# Stepper_control.net
KiCad netlist of a schematic drawn in Altium Designer
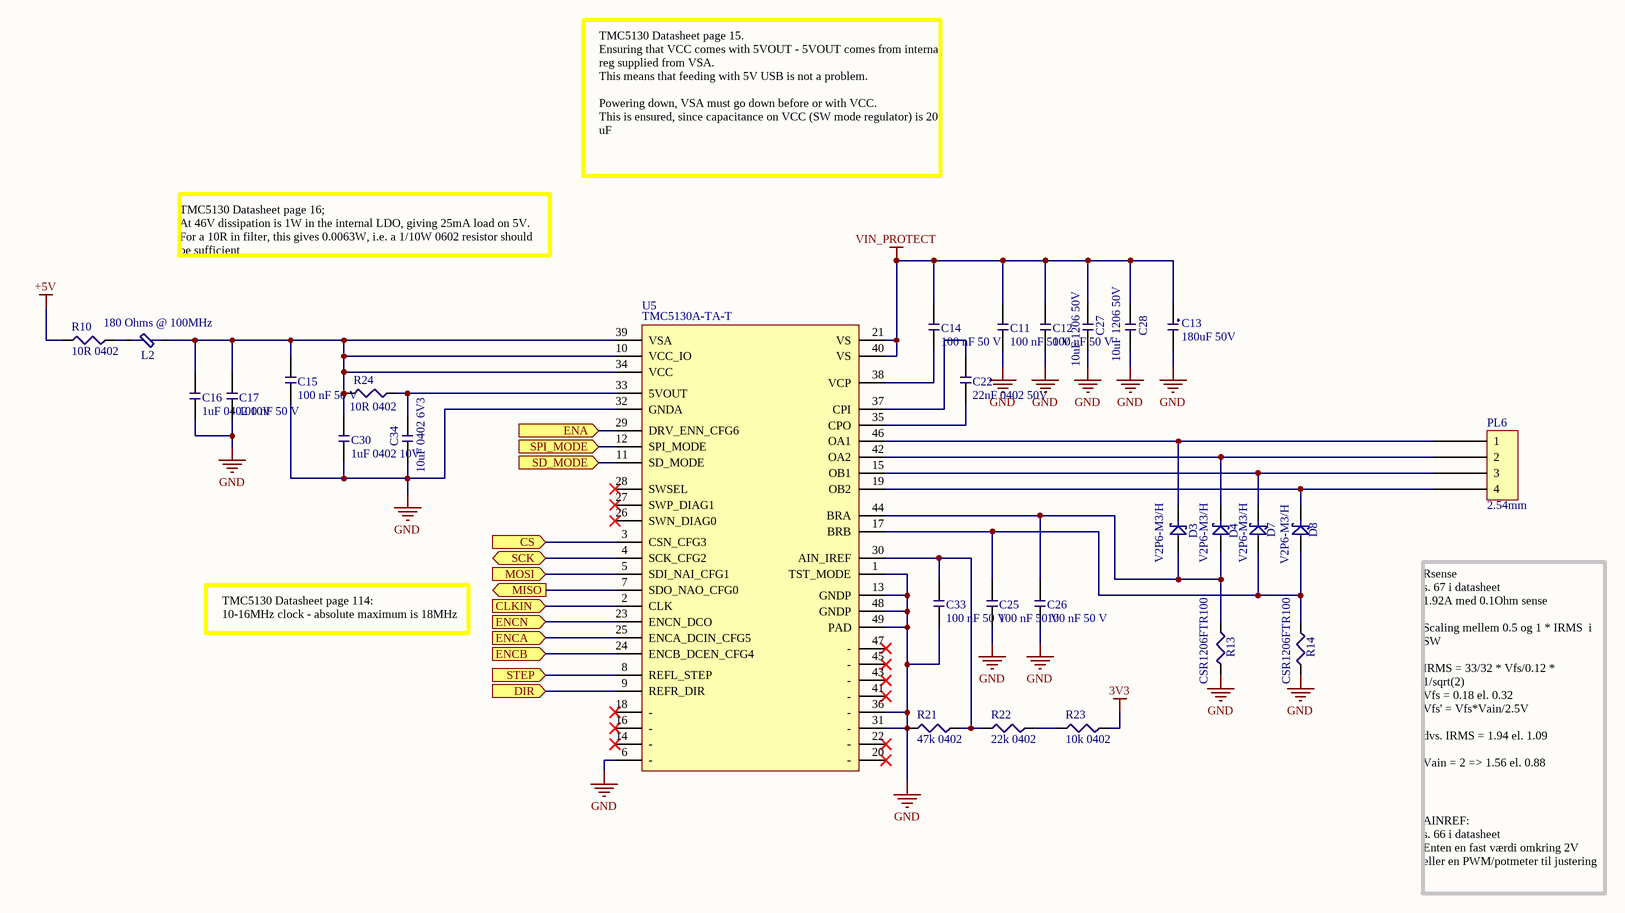
[diagram p0: Stepper_control.SchDoc]

(export (version "E")
  (design (tool "Eeschema 10.0.6"))
  (components
    (comp (ref "C11")
      (value "100 nF 50 V")
      (footprint "CAP_0402")
      (description "Multilayer Ceramic Capacitors MLCC - SMD/SMT .1uF 50Volts X7R +/-10% 0402 STD")
      (fields (field (name "TOLERANCE") "10%") (field (name "VOLTAGE") "50 V"))
      (libsource (lib "ON Development Vault") (part "Capacitor"))
    )
    (comp (ref "C12")
      (value "100 nF 50 V")
      (footprint "CAP_0402")
      (description "Multilayer Ceramic Capacitors MLCC - SMD/SMT .1uF 50Volts X7R +/-10% 0402 STD")
      (fields (field (name "TOLERANCE") "10%") (field (name "VOLTAGE") "50 V"))
      (libsource (lib "ON Development Vault") (part "Capacitor"))
    )
    (comp (ref "C13")
      (value "180uF 50V")
      (footprint "Capacitor 8x22")
      (description "180UF 20% 50V 105DEG RADIAL")
      (fields (field (name "TOLERANCE") "20%"))
      (libsource (lib "ON Development Vault") (part "Polar capacitor"))
    )
    (comp (ref "C14")
      (value "100 nF 50 V")
      (footprint "CAP_0402")
      (description "Multilayer Ceramic Capacitors MLCC - SMD/SMT .1uF 50Volts X7R +/-10% 0402 STD")
      (fields (field (name "TOLERANCE") "10%") (field (name "VOLTAGE") "50 V"))
      (libsource (lib "ON Development Vault") (part "Capacitor"))
    )
    (comp (ref "C15")
      (value "100 nF 50 V")
      (footprint "CAP_0402")
      (description "Multilayer Ceramic Capacitors MLCC - SMD/SMT .1uF 50Volts X7R +/-10% 0402 STD")
      (fields (field (name "TOLERANCE") "10%") (field (name "VOLTAGE") "50 V"))
      (libsource (lib "ON Development Vault") (part "Capacitor"))
    )
    (comp (ref "C16")
      (value "1uF 0402 10V")
      (footprint "CAP_0402")
      (description "1uF 0402 10V 10% X5R")
      (fields (field (name "TOLERANCE") "10%") (field (name "VOLTAGE") "10 V"))
      (libsource (lib "ON Development Vault") (part "Capacitor"))
    )
    (comp (ref "C17")
      (value "100 nF 50 V")
      (footprint "CAP_0402")
      (description "Multilayer Ceramic Capacitors MLCC - SMD/SMT .1uF 50Volts X7R +/-10% 0402 STD")
      (fields (field (name "TOLERANCE") "10%") (field (name "VOLTAGE") "50 V"))
      (libsource (lib "ON Development Vault") (part "Capacitor"))
    )
    (comp (ref "C22")
      (value "22nF 0402 50V")
      (footprint "CAP_0402")
      (description "22nF 0402 50V X7R 10%")
      (fields (field (name "TOLERANCE") "10%") (field (name "VOLTAGE") "50V"))
      (libsource (lib "ON Development Vault") (part "Capacitor"))
    )
    (comp (ref "C25")
      (value "100 nF 50 V")
      (footprint "CAP_0402")
      (description "Multilayer Ceramic Capacitors MLCC - SMD/SMT .1uF 50Volts X7R +/-10% 0402 STD")
      (fields (field (name "TOLERANCE") "10%") (field (name "VOLTAGE") "50 V"))
      (libsource (lib "ON Development Vault") (part "Capacitor"))
    )
    (comp (ref "C26")
      (value "100 nF 50 V")
      (footprint "CAP_0402")
      (description "Multilayer Ceramic Capacitors MLCC - SMD/SMT .1uF 50Volts X7R +/-10% 0402 STD")
      (fields (field (name "TOLERANCE") "10%") (field (name "VOLTAGE") "50 V"))
      (libsource (lib "ON Development Vault") (part "Capacitor"))
    )
    (comp (ref "C27")
      (value "10uF 1206 50V")
      (footprint "CAP_1206")
      (description "10uF 1206 50V X5R 20%")
      (fields (field (name "TOLERANCE") "+/- 20%") (field (name "VOLTAGE") "50 V"))
      (libsource (lib "ON Development Vault") (part "Capacitor"))
    )
    (comp (ref "C28")
      (value "10uF 1206 50V")
      (footprint "CAP_1206")
      (description "10uF 1206 50V X5R 20%")
      (fields (field (name "TOLERANCE") "+/- 20%") (field (name "VOLTAGE") "50 V"))
      (libsource (lib "ON Development Vault") (part "Capacitor"))
    )
    (comp (ref "C30")
      (value "1uF 0402 10V")
      (footprint "CAP_0402")
      (description "1uF 0402 10V 10% X5R")
      (fields (field (name "TOLERANCE") "10%") (field (name "VOLTAGE") "10 V"))
      (libsource (lib "ON Development Vault") (part "Capacitor"))
    )
    (comp (ref "C33")
      (value "100 nF 50 V")
      (footprint "CAP_0402")
      (description "Multilayer Ceramic Capacitors MLCC - SMD/SMT .1uF 50Volts X7R +/-10% 0402 STD")
      (fields (field (name "TOLERANCE") "10%") (field (name "VOLTAGE") "50 V"))
      (libsource (lib "ON Development Vault") (part "Capacitor"))
    )
    (comp (ref "C34")
      (value "10uF 0402 6V3")
      (footprint "CAP_0402")
      (description "10uF 20% 0402 6V3 X6S")
      (fields (field (name "TOLERANCE") "20%") (field (name "VOLTAGE") "6V3"))
      (libsource (lib "ON Development Vault") (part "Capacitor"))
    )
    (comp (ref "D3")
      (value "V2P6-M3/H")
      (footprint "MicroSMP")
      (description "DIODE SCHOTTKY 60V 2A MICROSMP")
      (libsource (lib "ON Development Vault") (part "Schottky"))
    )
    (comp (ref "D4")
      (value "V2P6-M3/H")
      (footprint "MicroSMP")
      (description "DIODE SCHOTTKY 60V 2A MICROSMP")
      (libsource (lib "ON Development Vault") (part "Schottky"))
    )
    (comp (ref "D7")
      (value "V2P6-M3/H")
      (footprint "MicroSMP")
      (description "DIODE SCHOTTKY 60V 2A MICROSMP")
      (libsource (lib "ON Development Vault") (part "Schottky"))
    )
    (comp (ref "D8")
      (value "V2P6-M3/H")
      (footprint "MicroSMP")
      (description "DIODE SCHOTTKY 60V 2A MICROSMP")
      (libsource (lib "ON Development Vault") (part "Schottky"))
    )
    (comp (ref "L2")
      (value "180 Ohms @ 100MHz")
      (footprint "IND_0603")
      (description "FERRITE BEAD 180 OHM 0603 1LN")
      (fields (field (name "MFG. PART NUMBER") "BLM18PG181SN1D"))
      (libsource (lib "ON Development Vault") (part "Ferrite"))
    )
    (comp (ref "PL6")
      (value "2.54mm")
      (footprint "4-pin 2.54mm header")
      (description "Pin header 4-pin 2.54mm male")
      (fields (field (name "MFG. PART NUMBER") "DS1021-1*4SF1-1"))
      (libsource (lib "ON Development Vault") (part "4-pin header"))
    )
    (comp (ref "R10")
      (value "10R 0402")
      (footprint "RES_0402")
      (description "RES SMD 10 OHM 1% 1/16W 0402")
      (fields (field (name "POWER") "63mW") (field (name "TOLERANCE") "1%"))
      (libsource (lib "ON Development Vault") (part "Resistor"))
    )
    (comp (ref "R13")
      (value "CSR1206FTR100")
      (footprint "RES_1206")
      (description "RES 0.1 OHM 1% 1/2W 1206")
      (fields (field (name "POWER") "0.5W") (field (name "TOLERANCE") "1%"))
      (libsource (lib "ON Development Vault") (part "Resistor"))
    )
    (comp (ref "R14")
      (value "CSR1206FTR100")
      (footprint "RES_1206")
      (description "RES 0.1 OHM 1% 1/2W 1206")
      (fields (field (name "POWER") "0.5W") (field (name "TOLERANCE") "1%"))
      (libsource (lib "ON Development Vault") (part "Resistor"))
    )
    (comp (ref "R21")
      (value "47k 0402")
      (footprint "RES_0402")
      (description "RES SMD 47K OHM 1% 1/16W 0402")
      (fields (field (name "POWER") "1/16W") (field (name "TOLERANCE") "1%"))
      (libsource (lib "ON Development Vault") (part "Resistor"))
    )
    (comp (ref "R22")
      (value "22k 0402")
      (footprint "RES_0402")
      (description "RES SMD 22K OHM 1% 1/16W 0402")
      (fields (field (name "POWER") "1/16W") (field (name "TOLERANCE") "1%"))
      (libsource (lib "ON Development Vault") (part "Resistor"))
    )
    (comp (ref "R23")
      (value "10k 0402")
      (footprint "RES_0402")
      (description "RES SMD 10K OHM 1% 1/16W 0402")
      (fields (field (name "POWER") "1/16 W") (field (name "TOLERANCE") "1 %"))
      (libsource (lib "ON Development Vault") (part "Resistor"))
    )
    (comp (ref "R24")
      (value "10R 0402")
      (footprint "RES_0402")
      (description "RES SMD 10 OHM 1% 1/16W 0402")
      (fields (field (name "POWER") "63mW") (field (name "TOLERANCE") "1%"))
      (libsource (lib "ON Development Vault") (part "Resistor"))
    )
    (comp (ref "U5")
      (value "TMC5130A-TA-T")
      (footprint "TSQFP50P900X900X120_HS-49N")
      (description "IC MOTOR CTLR/DVR SPI 48QFP")
      (libsource (lib "ON Development Vault") (part "TMC5130A-TA"))
    )
  )
  (nets
    (net (code "1") (name "+5V") (class "Default")
      (node (ref "R10") (pin "2") (pinfunction "2_2") (pintype "passive"))
    )
    (net (code "2") (name "/CLKIN") (class "Default")
      (node (ref "U5") (pin "2") (pinfunction "CLK_2") (pintype "passive"))
    )
    (net (code "3") (name "/CS") (class "Default")
      (node (ref "U5") (pin "3") (pinfunction "CSN_CFG3_3") (pintype "passive"))
    )
    (net (code "4") (name "/DIR") (class "Default")
      (node (ref "U5") (pin "9") (pinfunction "REFR_DIR_9") (pintype "passive"))
    )
    (net (code "5") (name "/ENA") (class "Default")
      (node (ref "U5") (pin "29") (pinfunction "DRV_ENN_CFG6_29") (pintype "passive"))
    )
    (net (code "6") (name "/ENCA") (class "Default")
      (node (ref "U5") (pin "25") (pinfunction "ENCA_DCIN_CFG5_25") (pintype "passive"))
    )
    (net (code "7") (name "/ENCB") (class "Default")
      (node (ref "U5") (pin "24") (pinfunction "ENCB_DCEN_CFG4_24") (pintype "passive"))
    )
    (net (code "8") (name "/ENCN") (class "Default")
      (node (ref "U5") (pin "23") (pinfunction "ENCN_DCO_23") (pintype "passive"))
    )
    (net (code "9") (name "/MISO") (class "Default")
      (node (ref "U5") (pin "7") (pinfunction "SDO_NAO_CFG0_7") (pintype "passive"))
    )
    (net (code "10") (name "/MOSI") (class "Default")
      (node (ref "U5") (pin "5") (pinfunction "SDI_NAI_CFG1_5") (pintype "passive"))
    )
    (net (code "11") (name "/SCK") (class "Default")
      (node (ref "U5") (pin "4") (pinfunction "SCK_CFG2_4") (pintype "passive"))
    )
    (net (code "12") (name "/SD_MODE") (class "Default")
      (node (ref "U5") (pin "11") (pinfunction "SD_MODE_11") (pintype "passive"))
    )
    (net (code "13") (name "/SPI_MODE") (class "Default")
      (node (ref "U5") (pin "12") (pinfunction "SPI_MODE_12") (pintype "passive"))
    )
    (net (code "14") (name "/STEP") (class "Default")
      (node (ref "U5") (pin "8") (pinfunction "REFL_STEP_8") (pintype "passive"))
    )
    (net (code "15") (name "3V3") (class "Default")
      (node (ref "R23") (pin "1") (pinfunction "1_1") (pintype "passive"))
    )
    (net (code "16") (name "GND") (class "Default")
      (node (ref "C11") (pin "2") (pinfunction "2_2") (pintype "passive"))
      (node (ref "C12") (pin "2") (pinfunction "2_2") (pintype "passive"))
      (node (ref "C13") (pin "2") (pinfunction "2_2") (pintype "passive"))
      (node (ref "C15") (pin "2") (pinfunction "2_2") (pintype "passive"))
      (node (ref "C16") (pin "1") (pinfunction "1_1") (pintype "passive"))
      (node (ref "C17") (pin "2") (pinfunction "2_2") (pintype "passive"))
      (node (ref "C25") (pin "2") (pinfunction "2_2") (pintype "passive"))
      (node (ref "C26") (pin "2") (pinfunction "2_2") (pintype "passive"))
      (node (ref "C27") (pin "2") (pinfunction "2_2") (pintype "passive"))
      (node (ref "C28") (pin "2") (pinfunction "2_2") (pintype "passive"))
      (node (ref "C30") (pin "1") (pinfunction "1_1") (pintype "passive"))
      (node (ref "C33") (pin "2") (pinfunction "2_2") (pintype "passive"))
      (node (ref "C34") (pin "1") (pinfunction "1_1") (pintype "passive"))
      (node (ref "R13") (pin "1") (pinfunction "1_1") (pintype "passive"))
      (node (ref "R14") (pin "1") (pinfunction "1_1") (pintype "passive"))
      (node (ref "R21") (pin "2") (pinfunction "2_2") (pintype "passive"))
      (node (ref "U5") (pin "1") (pinfunction "TST_MODE_1") (pintype "passive"))
      (node (ref "U5") (pin "13") (pinfunction "GNDP_13") (pintype "passive"))
      (node (ref "U5") (pin "31") (pinfunction "-_31") (pintype "passive"))
      (node (ref "U5") (pin "32") (pinfunction "GNDA_32") (pintype "passive"))
      (node (ref "U5") (pin "36") (pinfunction "-_36") (pintype "passive"))
      (node (ref "U5") (pin "48") (pinfunction "GNDP_48") (pintype "passive"))
      (node (ref "U5") (pin "49") (pinfunction "PAD_49") (pintype "passive"))
      (node (ref "U5") (pin "6") (pinfunction "-_6") (pintype "passive"))
    )
    (net (code "17") (name "Net-(L2-Pad1)") (class "Default")
      (node (ref "L2") (pin "1") (pinfunction "1_1") (pintype "passive"))
      (node (ref "R10") (pin "1") (pinfunction "1_1") (pintype "passive"))
    )
    (net (code "18") (name "Net-(R22-Pad2)") (class "Default")
      (node (ref "R22") (pin "2") (pinfunction "2_2") (pintype "passive"))
      (node (ref "R23") (pin "2") (pinfunction "2_2") (pintype "passive"))
    )
    (net (code "19") (name "Net-(U5-5VOUT)") (class "Default")
      (node (ref "C34") (pin "2") (pinfunction "2_2") (pintype "passive"))
      (node (ref "R24") (pin "2") (pinfunction "2_2") (pintype "passive"))
      (node (ref "U5") (pin "33") (pinfunction "5VOUT_33") (pintype "passive"))
    )
    (net (code "20") (name "Net-(U5-AIN_IREF)") (class "Default")
      (node (ref "C33") (pin "1") (pinfunction "1_1") (pintype "passive"))
      (node (ref "R21") (pin "1") (pinfunction "1_1") (pintype "passive"))
      (node (ref "R22") (pin "1") (pinfunction "1_1") (pintype "passive"))
      (node (ref "U5") (pin "30") (pinfunction "AIN_IREF_30") (pintype "passive"))
    )
    (net (code "21") (name "Net-(U5-BRA)") (class "Default")
      (node (ref "C26") (pin "1") (pinfunction "1_1") (pintype "passive"))
      (node (ref "D3") (pin "1") (pinfunction "1_1") (pintype "passive"))
      (node (ref "D4") (pin "1") (pinfunction "1_1") (pintype "passive"))
      (node (ref "R13") (pin "2") (pinfunction "2_2") (pintype "passive"))
      (node (ref "U5") (pin "44") (pinfunction "BRA_44") (pintype "passive"))
    )
    (net (code "22") (name "Net-(U5-BRB)") (class "Default")
      (node (ref "C25") (pin "1") (pinfunction "1_1") (pintype "passive"))
      (node (ref "D7") (pin "1") (pinfunction "1_1") (pintype "passive"))
      (node (ref "D8") (pin "1") (pinfunction "1_1") (pintype "passive"))
      (node (ref "R14") (pin "2") (pinfunction "2_2") (pintype "passive"))
      (node (ref "U5") (pin "17") (pinfunction "BRB_17") (pintype "passive"))
    )
    (net (code "23") (name "Net-(U5-CPI)") (class "Default")
      (node (ref "C22") (pin "2") (pinfunction "2_2") (pintype "passive"))
      (node (ref "U5") (pin "37") (pinfunction "CPI_37") (pintype "passive"))
    )
    (net (code "24") (name "Net-(U5-CPO)") (class "Default")
      (node (ref "C22") (pin "1") (pinfunction "1_1") (pintype "passive"))
      (node (ref "U5") (pin "35") (pinfunction "CPO_35") (pintype "passive"))
    )
    (net (code "25") (name "Net-(U5-OA1)") (class "Default")
      (node (ref "D3") (pin "2") (pinfunction "2_2") (pintype "passive"))
      (node (ref "PL6") (pin "1") (pinfunction "1_1") (pintype "passive"))
      (node (ref "U5") (pin "46") (pinfunction "OA1_46") (pintype "passive"))
    )
    (net (code "26") (name "Net-(U5-OA2)") (class "Default")
      (node (ref "D4") (pin "2") (pinfunction "2_2") (pintype "passive"))
      (node (ref "PL6") (pin "2") (pinfunction "2_2") (pintype "passive"))
      (node (ref "U5") (pin "42") (pinfunction "OA2_42") (pintype "passive"))
    )
    (net (code "27") (name "Net-(U5-OB1)") (class "Default")
      (node (ref "D7") (pin "2") (pinfunction "2_2") (pintype "passive"))
      (node (ref "PL6") (pin "3") (pinfunction "3_3") (pintype "passive"))
      (node (ref "U5") (pin "15") (pinfunction "OB1_15") (pintype "passive"))
    )
    (net (code "28") (name "Net-(U5-OB2)") (class "Default")
      (node (ref "D8") (pin "2") (pinfunction "2_2") (pintype "passive"))
      (node (ref "PL6") (pin "4") (pinfunction "4_4") (pintype "passive"))
      (node (ref "U5") (pin "19") (pinfunction "OB2_19") (pintype "passive"))
    )
    (net (code "29") (name "Net-(U5-VCC)") (class "Default")
      (node (ref "C15") (pin "1") (pinfunction "1_1") (pintype "passive"))
      (node (ref "C16") (pin "2") (pinfunction "2_2") (pintype "passive"))
      (node (ref "C17") (pin "1") (pinfunction "1_1") (pintype "passive"))
      (node (ref "C30") (pin "2") (pinfunction "2_2") (pintype "passive"))
      (node (ref "L2") (pin "2") (pinfunction "2_2") (pintype "passive"))
      (node (ref "R24") (pin "1") (pinfunction "1_1") (pintype "passive"))
      (node (ref "U5") (pin "10") (pinfunction "VCC_IO_10") (pintype "passive"))
      (node (ref "U5") (pin "34") (pinfunction "VCC_34") (pintype "passive"))
      (node (ref "U5") (pin "39") (pinfunction "VSA_39") (pintype "passive"))
    )
    (net (code "30") (name "Net-(U5-VCP)") (class "Default")
      (node (ref "C14") (pin "1") (pinfunction "1_1") (pintype "passive"))
      (node (ref "U5") (pin "38") (pinfunction "VCP_38") (pintype "passive"))
    )
    (net (code "31") (name "VIN_PROTECT") (class "Default")
      (node (ref "C11") (pin "1") (pinfunction "1_1") (pintype "passive"))
      (node (ref "C12") (pin "1") (pinfunction "1_1") (pintype "passive"))
      (node (ref "C13") (pin "1") (pinfunction "1_1") (pintype "passive"))
      (node (ref "C14") (pin "2") (pinfunction "2_2") (pintype "passive"))
      (node (ref "C27") (pin "1") (pinfunction "1_1") (pintype "passive"))
      (node (ref "C28") (pin "1") (pinfunction "1_1") (pintype "passive"))
      (node (ref "U5") (pin "21") (pinfunction "VS_21") (pintype "passive"))
      (node (ref "U5") (pin "40") (pinfunction "VS_40") (pintype "passive"))
    )
    (net (code "32") (name "unconnected-(U5---Pad14)") (class "Default")
      (node (ref "U5") (pin "14") (pinfunction "-_14") (pintype "passive+no_connect"))
    )
    (net (code "33") (name "unconnected-(U5---Pad16)") (class "Default")
      (node (ref "U5") (pin "16") (pinfunction "-_16") (pintype "passive+no_connect"))
    )
    (net (code "34") (name "unconnected-(U5---Pad18)") (class "Default")
      (node (ref "U5") (pin "18") (pinfunction "-_18") (pintype "passive+no_connect"))
    )
    (net (code "35") (name "unconnected-(U5---Pad20)") (class "Default")
      (node (ref "U5") (pin "20") (pinfunction "-_20") (pintype "passive+no_connect"))
    )
    (net (code "36") (name "unconnected-(U5---Pad22)") (class "Default")
      (node (ref "U5") (pin "22") (pinfunction "-_22") (pintype "passive+no_connect"))
    )
    (net (code "37") (name "unconnected-(U5---Pad41)") (class "Default")
      (node (ref "U5") (pin "41") (pinfunction "-_41") (pintype "passive+no_connect"))
    )
    (net (code "38") (name "unconnected-(U5---Pad43)") (class "Default")
      (node (ref "U5") (pin "43") (pinfunction "-_43") (pintype "passive+no_connect"))
    )
    (net (code "39") (name "unconnected-(U5---Pad45)") (class "Default")
      (node (ref "U5") (pin "45") (pinfunction "-_45") (pintype "passive+no_connect"))
    )
    (net (code "40") (name "unconnected-(U5---Pad47)") (class "Default")
      (node (ref "U5") (pin "47") (pinfunction "-_47") (pintype "passive+no_connect"))
    )
    (net (code "41") (name "unconnected-(U5-SWN_DIAG0-Pad26)") (class "Default")
      (node (ref "U5") (pin "26") (pinfunction "SWN_DIAG0_26") (pintype "passive+no_connect"))
    )
    (net (code "42") (name "unconnected-(U5-SWP_DIAG1-Pad27)") (class "Default")
      (node (ref "U5") (pin "27") (pinfunction "SWP_DIAG1_27") (pintype "passive+no_connect"))
    )
    (net (code "43") (name "unconnected-(U5-SWSEL-Pad28)") (class "Default")
      (node (ref "U5") (pin "28") (pinfunction "SWSEL_28") (pintype "passive+no_connect"))
    )
  )
)
